# SCH_dito_2026-01-28.net
KiCad netlist of a schematic drawn in EasyEDA
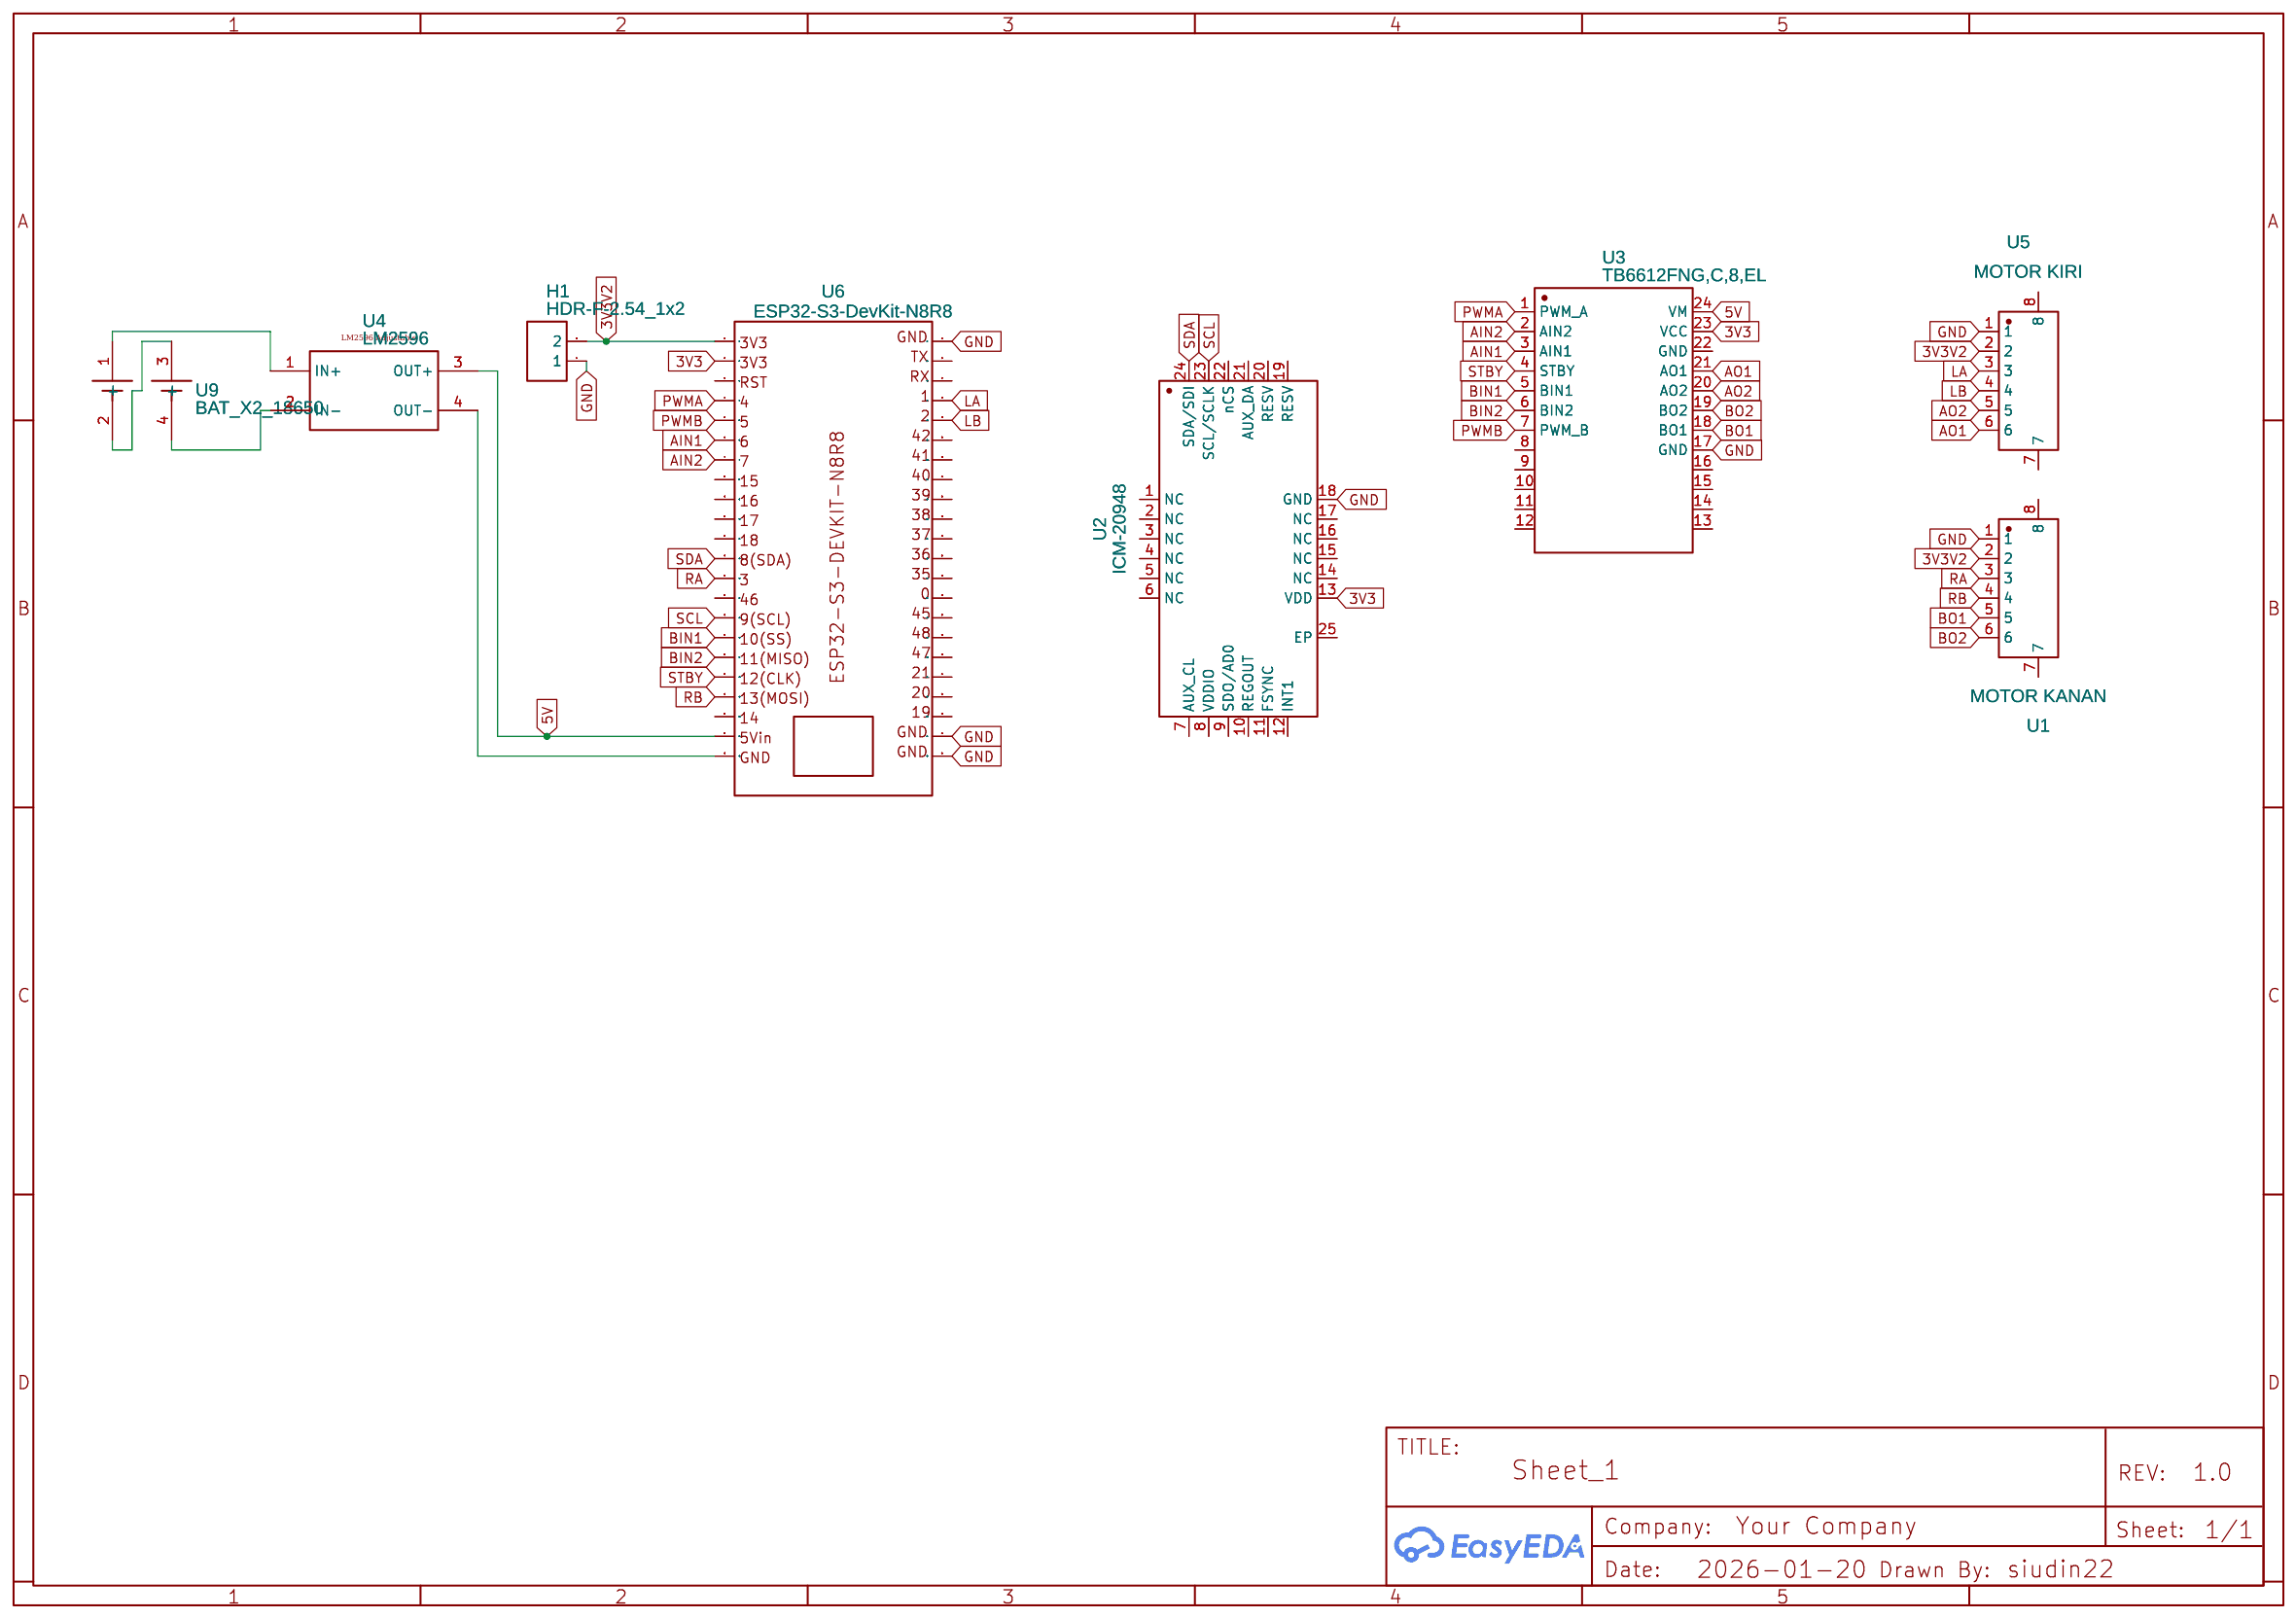
[diagram p0: Sheet_1]
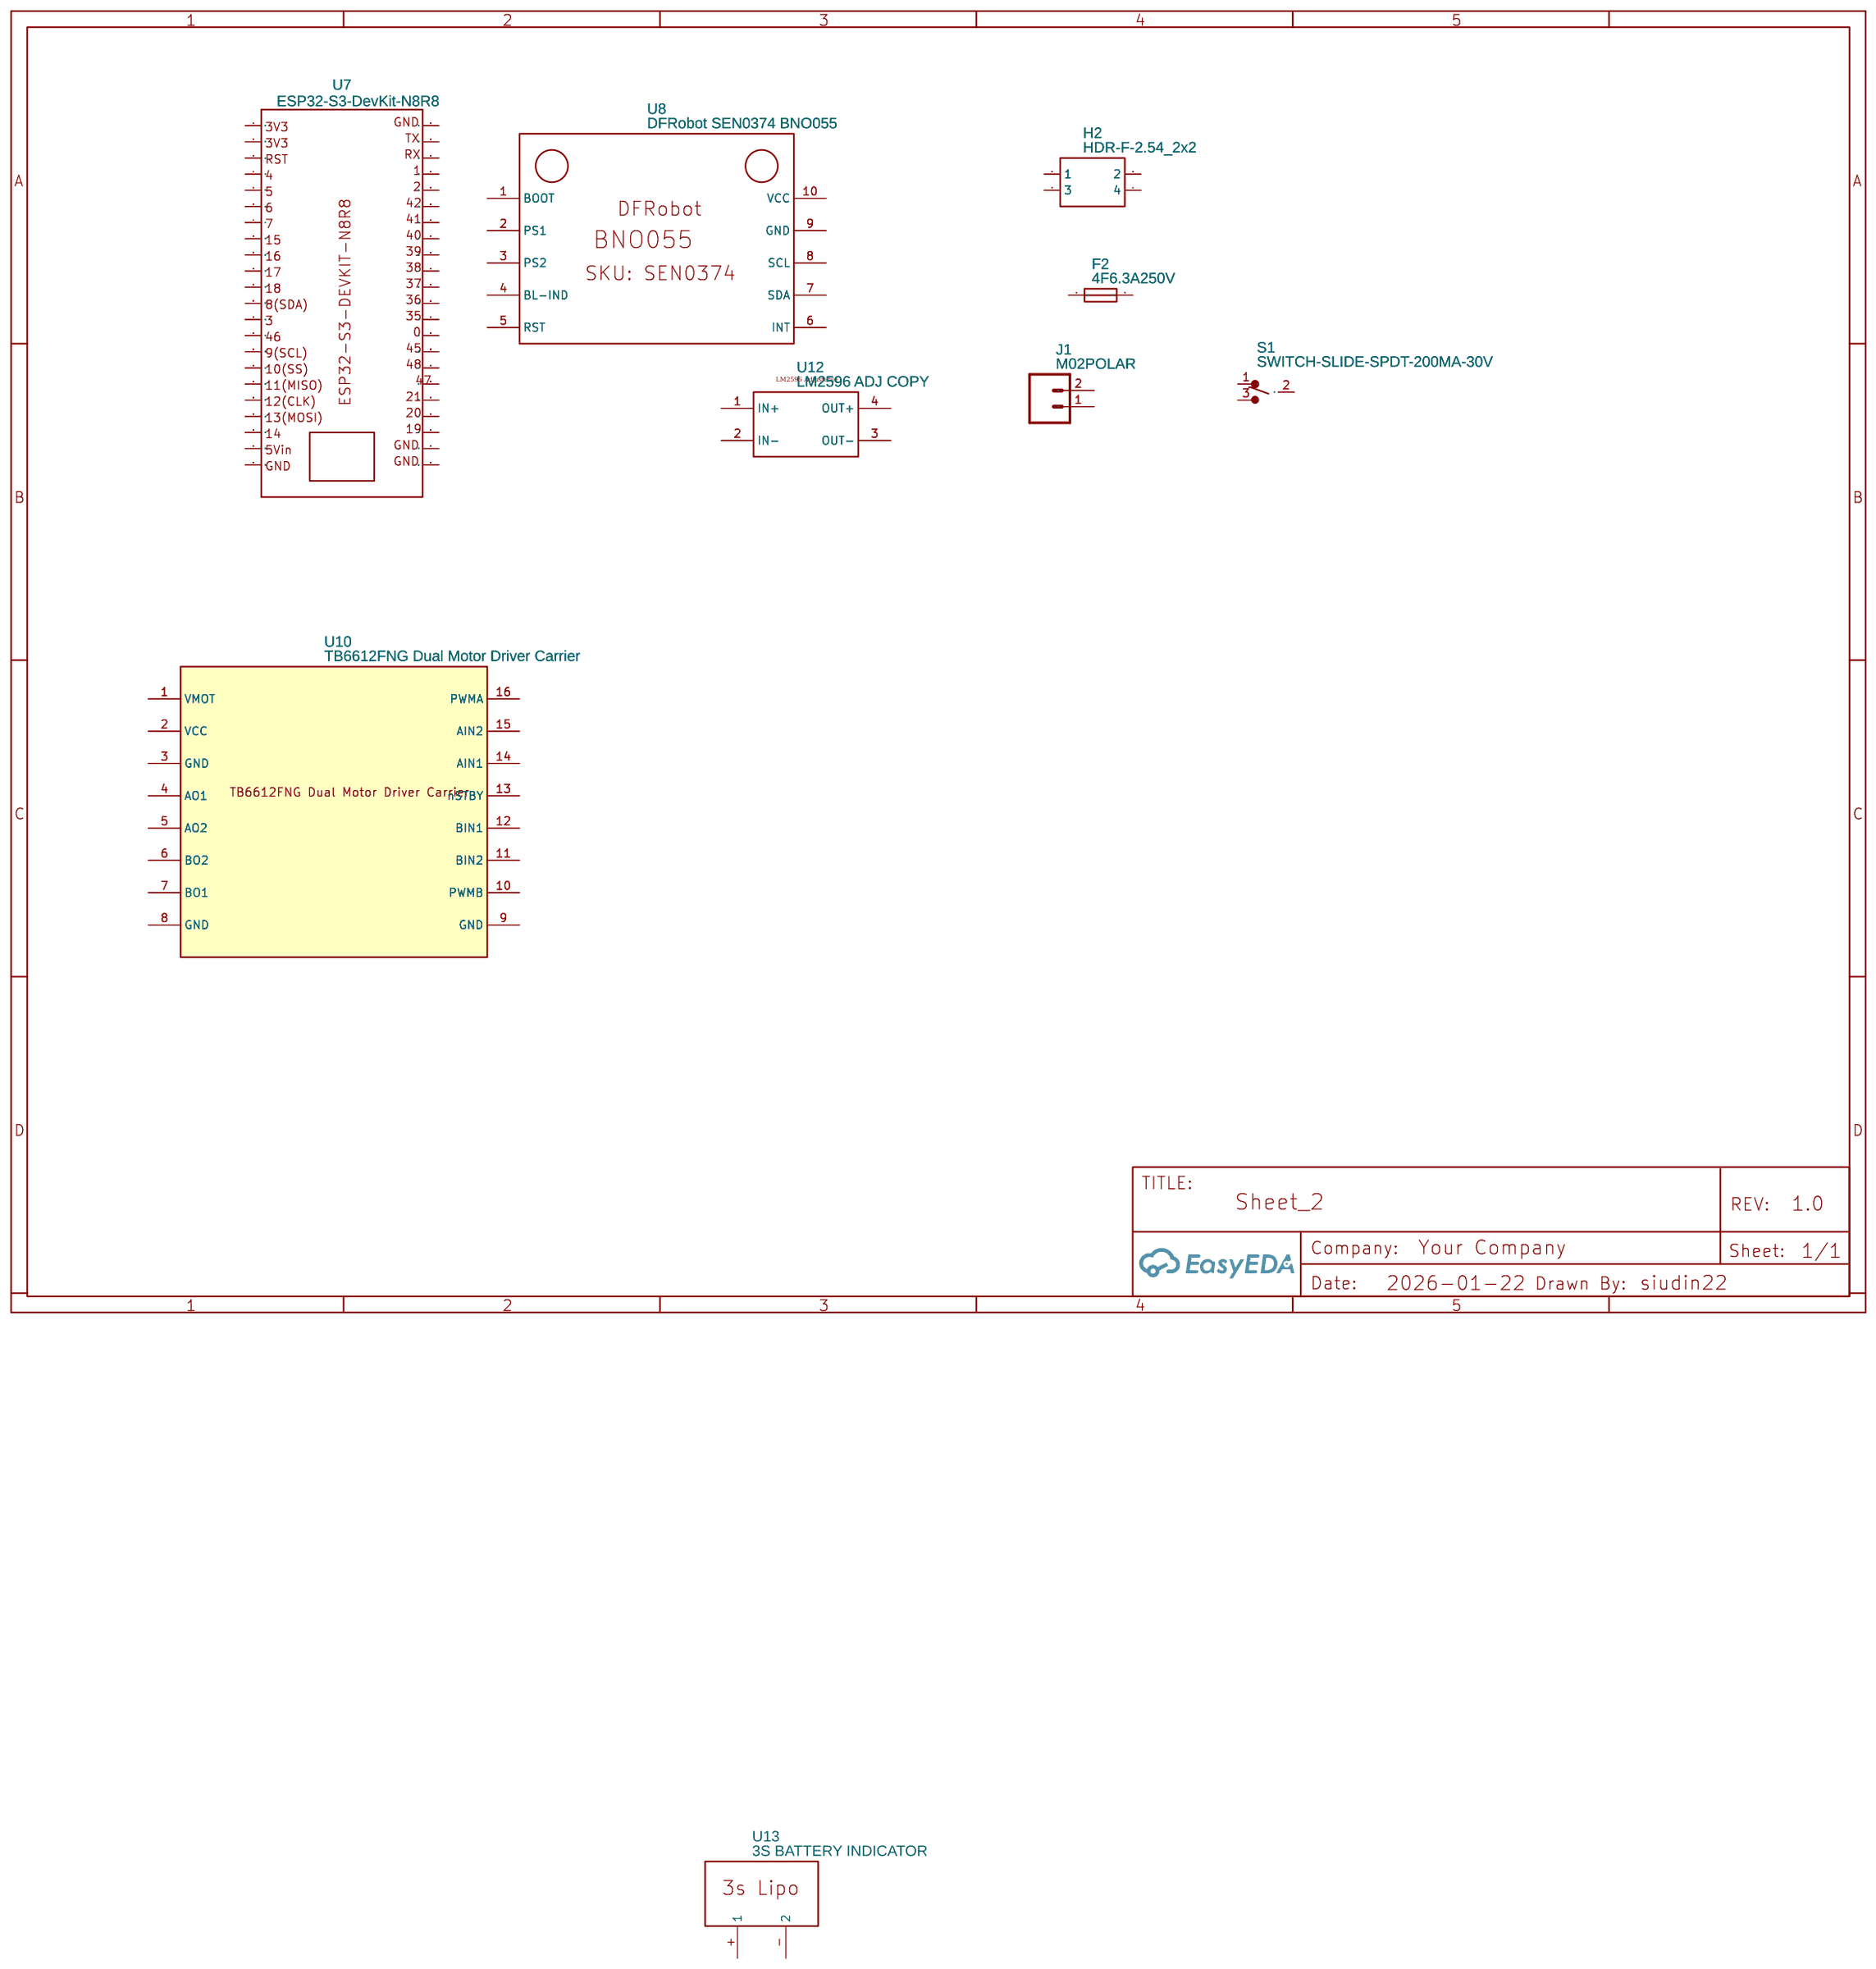
[diagram p1: Sheet_2]

(export (version "E")
  (design (tool "Eeschema 10.0.6"))
  (components
    (comp (ref "H1") (value "HDR-F-2.54_1x2") (libsource (lib "") (part "HDR-F-2.54_1x2")))
    (comp (ref "U1")
      (value "MOTOR KANAN")
      (fields (field (name "Manufacturer Part") "XY-SH1.0-6A61") (field (name "Manufacturer") "XYECONN(辛译)"))
      (libsource (lib "") (part "XY-SH1.0-6A61"))
    )
    (comp (ref "U2")
      (value "ICM-20948")
      (fields (field (name "Manufacturer") "TDK InvenSense(应美盛)"))
      (libsource (lib "") (part "ICM-20948"))
    )
    (comp (ref "U3")
      (value "TB6612FNG,C,8,EL")
      (fields (field (name "Manufacturer") "TOSHIBA(东芝)"))
      (libsource (lib "") (part "TB6612FNG,C,8,EL"))
    )
    (comp (ref "U4") (value "LM2596") (libsource (lib "") (part "BuckConverters_LM2596_Adj")))
    (comp (ref "U5")
      (value "MOTOR KIRI")
      (fields (field (name "Manufacturer Part") "XY-SH1.0-6A61") (field (name "Manufacturer") "XYECONN(辛译)"))
      (libsource (lib "") (part "XY-SH1.0-6A61"))
    )
    (comp (ref "U6")
      (value "ESP32-S3-DevKit-N8R8")
      (fields (field (name "Manufacturer") "WaveShare"))
      (libsource (lib "") (part "ESP32-S3-DevKit-N8R8"))
    )
    (comp (ref "U9")
      (value "BAT_X2_18650")
      (fields (field (name "Manufacturer") "Dex"))
      (libsource (lib "") (part "BAT_X2_18650"))
    )
    (comp (ref "F2")
      (value "4F6.3A250V")
      (fields (field (name "Manufacturer") "xcfuse(旭程)"))
      (libsource (lib "") (part "4F6.3A250V"))
    )
    (comp (ref "H2") (value "HDR-F-2.54_2x2") (libsource (lib "") (part "HDR-F-2.54_2x2")))
    (comp (ref "J1") (value "M02POLAR") (libsource (lib "") (part "M02POLAR")))
    (comp (ref "S1")
      (value "SWITCH-SLIDE-SPDT-200MA-30V")
      (libsource (lib "") (part "SWITCH-SLIDE-SPDT-200MA-30V"))
    )
    (comp (ref "U7")
      (value "ESP32-S3-DevKit-N8R8")
      (fields (field (name "Manufacturer") "WaveShare"))
      (libsource (lib "") (part "ESP32-S3-DevKit-N8R8"))
    )
    (comp (ref "U8") (value "DFRobot SEN0374 BNO055") (libsource (lib "") (part "DFRobot SEN0374 BNO055")))
    (comp (ref "U10")
      (value "TB6612FNG Dual Motor Driver Carrier")
      (libsource (lib "") (part "TB6612FNG Dual Motor Driver Carrier"))
    )
    (comp (ref "U12") (value "LM2596 ADJ COPY") (libsource (lib "") (part "BuckConverters_LM2596_Adj")))
    (comp (ref "U13") (value "3S BATTERY INDICATOR") (libsource (lib "") (part "3S BATTERY INDICATOR")))
  )
  (nets
    (net (code "1") (name "3V3") (class "Default")
      (node (ref "U2") (pin "13") (pinfunction "VDD_13") (pintype "unspecified"))
      (node (ref "U3") (pin "23") (pinfunction "VCC_23") (pintype "unspecified"))
      (node (ref "U6") (pin "2") (pinfunction "2_2") (pintype "unspecified"))
    )
    (net (code "2") (name "3V3V2") (class "Default")
      (node (ref "H1") (pin "2") (pinfunction "2_2") (pintype "input"))
      (node (ref "U1") (pin "2") (pinfunction "2_2") (pintype "unspecified"))
      (node (ref "U5") (pin "2") (pinfunction "2_2") (pintype "unspecified"))
      (node (ref "U6") (pin "1") (pinfunction "1_1") (pintype "unspecified"))
    )
    (net (code "3") (name "5V") (class "Default")
      (node (ref "U3") (pin "24") (pinfunction "VM_24") (pintype "unspecified"))
      (node (ref "U4") (pin "3") (pinfunction "OUT+_3") (pintype "unspecified"))
      (node (ref "U6") (pin "21") (pinfunction "21_21") (pintype "unspecified"))
    )
    (net (code "4") (name "AIN1") (class "Default")
      (node (ref "U3") (pin "3") (pinfunction "AIN1_3") (pintype "unspecified"))
      (node (ref "U6") (pin "6") (pinfunction "6_6") (pintype "unspecified"))
    )
    (net (code "5") (name "AIN2") (class "Default")
      (node (ref "U3") (pin "2") (pinfunction "AIN2_2") (pintype "unspecified"))
      (node (ref "U6") (pin "7") (pinfunction "7_7") (pintype "unspecified"))
    )
    (net (code "6") (name "AO1") (class "Default")
      (node (ref "U3") (pin "21") (pinfunction "AO1_21") (pintype "unspecified"))
      (node (ref "U5") (pin "6") (pinfunction "6_6") (pintype "unspecified"))
    )
    (net (code "7") (name "AO2") (class "Default")
      (node (ref "U3") (pin "20") (pinfunction "AO2_20") (pintype "unspecified"))
      (node (ref "U5") (pin "5") (pinfunction "5_5") (pintype "unspecified"))
    )
    (net (code "8") (name "BIN1") (class "Default")
      (node (ref "U3") (pin "5") (pinfunction "BIN1_5") (pintype "unspecified"))
      (node (ref "U6") (pin "16") (pinfunction "16_16") (pintype "unspecified"))
    )
    (net (code "9") (name "BIN2") (class "Default")
      (node (ref "U3") (pin "6") (pinfunction "BIN2_6") (pintype "unspecified"))
      (node (ref "U6") (pin "17") (pinfunction "17_17") (pintype "unspecified"))
    )
    (net (code "10") (name "BO1") (class "Default")
      (node (ref "U1") (pin "5") (pinfunction "5_5") (pintype "unspecified"))
      (node (ref "U3") (pin "18") (pinfunction "BO1_18") (pintype "unspecified"))
    )
    (net (code "11") (name "BO2") (class "Default")
      (node (ref "U1") (pin "6") (pinfunction "6_6") (pintype "unspecified"))
      (node (ref "U3") (pin "19") (pinfunction "BO2_19") (pintype "unspecified"))
    )
    (net (code "12") (name "GND") (class "Default")
      (node (ref "H1") (pin "1") (pinfunction "1_1") (pintype "input"))
      (node (ref "U1") (pin "1") (pinfunction "1_1") (pintype "unspecified"))
      (node (ref "U2") (pin "18") (pinfunction "GND_18") (pintype "unspecified"))
      (node (ref "U3") (pin "17") (pinfunction "GND_17") (pintype "unspecified"))
      (node (ref "U5") (pin "1") (pinfunction "1_1") (pintype "unspecified"))
      (node (ref "U6") (pin "23") (pinfunction "23_23") (pintype "unspecified"))
      (node (ref "U6") (pin "24") (pinfunction "24_24") (pintype "unspecified"))
      (node (ref "U6") (pin "44") (pinfunction "44_44") (pintype "unspecified"))
    )
    (net (code "13") (name "LA") (class "Default")
      (node (ref "U5") (pin "3") (pinfunction "3_3") (pintype "unspecified"))
      (node (ref "U6") (pin "41") (pinfunction "41_41") (pintype "unspecified"))
    )
    (net (code "14") (name "LB") (class "Default")
      (node (ref "U5") (pin "4") (pinfunction "4_4") (pintype "unspecified"))
      (node (ref "U6") (pin "40") (pinfunction "40_40") (pintype "unspecified"))
    )
    (net (code "15") (name "Net-(U4-IN+)") (class "Default")
      (node (ref "U4") (pin "1") (pinfunction "IN+_1") (pintype "unspecified"))
      (node (ref "U9") (pin "1") (pinfunction "+_1") (pintype "unspecified"))
    )
    (net (code "16") (name "Net-(U4-IN-)") (class "Default")
      (node (ref "U4") (pin "2") (pinfunction "IN-_2") (pintype "unspecified"))
      (node (ref "U9") (pin "4") (pinfunction "-_4") (pintype "unspecified"))
    )
    (net (code "17") (name "Net-(U4-OUT-)") (class "Default")
      (node (ref "U4") (pin "4") (pinfunction "OUT-_4") (pintype "unspecified"))
      (node (ref "U6") (pin "22") (pinfunction "22_22") (pintype "unspecified"))
    )
    (net (code "18") (name "Net-(U9-+-Pad3)") (class "Default")
      (node (ref "U9") (pin "2") (pinfunction "-_2") (pintype "unspecified"))
      (node (ref "U9") (pin "3") (pinfunction "+_3") (pintype "unspecified"))
    )
    (net (code "19") (name "PWMA") (class "Default")
      (node (ref "U3") (pin "1") (pinfunction "PWM_A_1") (pintype "unspecified"))
      (node (ref "U6") (pin "4") (pinfunction "4_4") (pintype "unspecified"))
    )
    (net (code "20") (name "PWMB") (class "Default")
      (node (ref "U3") (pin "7") (pinfunction "PWM_B_7") (pintype "unspecified"))
      (node (ref "U6") (pin "5") (pinfunction "5_5") (pintype "unspecified"))
    )
    (net (code "21") (name "RA") (class "Default")
      (node (ref "U1") (pin "3") (pinfunction "3_3") (pintype "unspecified"))
      (node (ref "U6") (pin "13") (pinfunction "13_13") (pintype "unspecified"))
    )
    (net (code "22") (name "RB") (class "Default")
      (node (ref "U1") (pin "4") (pinfunction "4_4") (pintype "unspecified"))
      (node (ref "U6") (pin "19") (pinfunction "19_19") (pintype "unspecified"))
    )
    (net (code "23") (name "SCL") (class "Default")
      (node (ref "U2") (pin "23") (pinfunction "SCL/SCLK_23") (pintype "unspecified"))
      (node (ref "U6") (pin "15") (pinfunction "15_15") (pintype "unspecified"))
    )
    (net (code "24") (name "SDA") (class "Default")
      (node (ref "U2") (pin "24") (pinfunction "SDA/SDI_24") (pintype "unspecified"))
      (node (ref "U6") (pin "12") (pinfunction "12_12") (pintype "unspecified"))
    )
    (net (code "25") (name "STBY") (class "Default")
      (node (ref "U3") (pin "4") (pinfunction "STBY_4") (pintype "unspecified"))
      (node (ref "U6") (pin "18") (pinfunction "18_18") (pintype "unspecified"))
    )
    (net (code "26") (name "unconnected-(F2-Pad1)") (class "Default")
      (node (ref "F2") (pin "1") (pinfunction "1_1") (pintype "unspecified"))
    )
    (net (code "27") (name "unconnected-(F2-Pad2)") (class "Default")
      (node (ref "F2") (pin "2") (pinfunction "2_2") (pintype "unspecified"))
    )
    (net (code "28") (name "unconnected-(H2-Pad1)") (class "Default")
      (node (ref "H2") (pin "1") (pinfunction "1_1") (pintype "unspecified"))
    )
    (net (code "29") (name "unconnected-(H2-Pad2)") (class "Default")
      (node (ref "H2") (pin "2") (pinfunction "2_2") (pintype "unspecified"))
    )
    (net (code "30") (name "unconnected-(H2-Pad3)") (class "Default")
      (node (ref "H2") (pin "3") (pinfunction "3_3") (pintype "unspecified"))
    )
    (net (code "31") (name "unconnected-(H2-Pad4)") (class "Default")
      (node (ref "H2") (pin "4") (pinfunction "4_4") (pintype "unspecified"))
    )
    (net (code "32") (name "unconnected-(J1-Pad1)") (class "Default")
      (node (ref "J1") (pin "1") (pinfunction "1_1") (pintype "bidirectional"))
    )
    (net (code "33") (name "unconnected-(J1-Pad2)") (class "Default")
      (node (ref "J1") (pin "2") (pinfunction "2_2") (pintype "bidirectional"))
    )
    (net (code "34") (name "unconnected-(S1-Pad1)") (class "Default")
      (node (ref "S1") (pin "1") (pinfunction "1_1") (pintype "input"))
    )
    (net (code "35") (name "unconnected-(S1-Pad2)") (class "Default")
      (node (ref "S1") (pin "2") (pinfunction "2_2") (pintype "input"))
    )
    (net (code "36") (name "unconnected-(S1-Pad3)") (class "Default")
      (node (ref "S1") (pin "3") (pinfunction "3_3") (pintype "input"))
    )
    (net (code "37") (name "unconnected-(U1-Pad7)") (class "Default")
      (node (ref "U1") (pin "7") (pinfunction "7_7") (pintype "unspecified"))
    )
    (net (code "38") (name "unconnected-(U1-Pad8)") (class "Default")
      (node (ref "U1") (pin "8") (pinfunction "8_8") (pintype "unspecified"))
    )
    (net (code "39") (name "unconnected-(U2-AUX_CL-Pad7)") (class "Default")
      (node (ref "U2") (pin "7") (pinfunction "AUX_CL_7") (pintype "unspecified"))
    )
    (net (code "40") (name "unconnected-(U2-AUX_DA-Pad21)") (class "Default")
      (node (ref "U2") (pin "21") (pinfunction "AUX_DA_21") (pintype "unspecified"))
    )
    (net (code "41") (name "unconnected-(U2-EP-Pad25)") (class "Default")
      (node (ref "U2") (pin "25") (pinfunction "EP_25") (pintype "unspecified"))
    )
    (net (code "42") (name "unconnected-(U2-FSYNC-Pad11)") (class "Default")
      (node (ref "U2") (pin "11") (pinfunction "FSYNC_11") (pintype "unspecified"))
    )
    (net (code "43") (name "unconnected-(U2-INT1-Pad12)") (class "Default")
      (node (ref "U2") (pin "12") (pinfunction "INT1_12") (pintype "unspecified"))
    )
    (net (code "44") (name "unconnected-(U2-NC-Pad1)") (class "Default")
      (node (ref "U2") (pin "1") (pinfunction "NC_1") (pintype "unspecified"))
    )
    (net (code "45") (name "unconnected-(U2-NC-Pad2)") (class "Default")
      (node (ref "U2") (pin "2") (pinfunction "NC_2") (pintype "unspecified"))
    )
    (net (code "46") (name "unconnected-(U2-NC-Pad3)") (class "Default")
      (node (ref "U2") (pin "3") (pinfunction "NC_3") (pintype "unspecified"))
    )
    (net (code "47") (name "unconnected-(U2-NC-Pad4)") (class "Default")
      (node (ref "U2") (pin "4") (pinfunction "NC_4") (pintype "unspecified"))
    )
    (net (code "48") (name "unconnected-(U2-NC-Pad5)") (class "Default")
      (node (ref "U2") (pin "5") (pinfunction "NC_5") (pintype "unspecified"))
    )
    (net (code "49") (name "unconnected-(U2-NC-Pad6)") (class "Default")
      (node (ref "U2") (pin "6") (pinfunction "NC_6") (pintype "unspecified"))
    )
    (net (code "50") (name "unconnected-(U2-NC-Pad14)") (class "Default")
      (node (ref "U2") (pin "14") (pinfunction "NC_14") (pintype "unspecified"))
    )
    (net (code "51") (name "unconnected-(U2-NC-Pad15)") (class "Default")
      (node (ref "U2") (pin "15") (pinfunction "NC_15") (pintype "unspecified"))
    )
    (net (code "52") (name "unconnected-(U2-NC-Pad16)") (class "Default")
      (node (ref "U2") (pin "16") (pinfunction "NC_16") (pintype "unspecified"))
    )
    (net (code "53") (name "unconnected-(U2-NC-Pad17)") (class "Default")
      (node (ref "U2") (pin "17") (pinfunction "NC_17") (pintype "unspecified"))
    )
    (net (code "54") (name "unconnected-(U2-REGOUT-Pad10)") (class "Default")
      (node (ref "U2") (pin "10") (pinfunction "REGOUT_10") (pintype "unspecified"))
    )
    (net (code "55") (name "unconnected-(U2-RESV-Pad19)") (class "Default")
      (node (ref "U2") (pin "19") (pinfunction "RESV_19") (pintype "unspecified"))
    )
    (net (code "56") (name "unconnected-(U2-RESV-Pad20)") (class "Default")
      (node (ref "U2") (pin "20") (pinfunction "RESV_20") (pintype "unspecified"))
    )
    (net (code "57") (name "unconnected-(U2-SDO{slash}AD0-Pad9)") (class "Default")
      (node (ref "U2") (pin "9") (pinfunction "SDO/AD0_9") (pintype "unspecified"))
    )
    (net (code "58") (name "unconnected-(U2-VDDIO-Pad8)") (class "Default")
      (node (ref "U2") (pin "8") (pinfunction "VDDIO_8") (pintype "unspecified"))
    )
    (net (code "59") (name "unconnected-(U2-nCS-Pad22)") (class "Default")
      (node (ref "U2") (pin "22") (pinfunction "nCS_22") (pintype "unspecified"))
    )
    (net (code "60") (name "unconnected-(U3-GND-Pad22)") (class "Default")
      (node (ref "U3") (pin "22") (pinfunction "GND_22") (pintype "unspecified"))
    )
    (net (code "61") (name "unconnected-(U3-Pad8)") (class "Default")
      (node (ref "U3") (pin "8") (pintype "unspecified"))
    )
    (net (code "62") (name "unconnected-(U3-Pad9)") (class "Default")
      (node (ref "U3") (pin "9") (pintype "unspecified"))
    )
    (net (code "63") (name "unconnected-(U3-Pad10)") (class "Default")
      (node (ref "U3") (pin "10") (pintype "unspecified"))
    )
    (net (code "64") (name "unconnected-(U3-Pad11)") (class "Default")
      (node (ref "U3") (pin "11") (pintype "unspecified"))
    )
    (net (code "65") (name "unconnected-(U3-Pad12)") (class "Default")
      (node (ref "U3") (pin "12") (pintype "unspecified"))
    )
    (net (code "66") (name "unconnected-(U3-Pad13)") (class "Default")
      (node (ref "U3") (pin "13") (pintype "unspecified"))
    )
    (net (code "67") (name "unconnected-(U3-Pad14)") (class "Default")
      (node (ref "U3") (pin "14") (pintype "unspecified"))
    )
    (net (code "68") (name "unconnected-(U3-Pad15)") (class "Default")
      (node (ref "U3") (pin "15") (pintype "unspecified"))
    )
    (net (code "69") (name "unconnected-(U3-Pad16)") (class "Default")
      (node (ref "U3") (pin "16") (pintype "unspecified"))
    )
    (net (code "70") (name "unconnected-(U5-Pad7)") (class "Default")
      (node (ref "U5") (pin "7") (pinfunction "7_7") (pintype "unspecified"))
    )
    (net (code "71") (name "unconnected-(U5-Pad8)") (class "Default")
      (node (ref "U5") (pin "8") (pinfunction "8_8") (pintype "unspecified"))
    )
    (net (code "72") (name "unconnected-(U6-Pad3)") (class "Default")
      (node (ref "U6") (pin "3") (pinfunction "3_3") (pintype "unspecified"))
    )
    (net (code "73") (name "unconnected-(U6-Pad8)") (class "Default")
      (node (ref "U6") (pin "8") (pinfunction "8_8") (pintype "unspecified"))
    )
    (net (code "74") (name "unconnected-(U6-Pad9)") (class "Default")
      (node (ref "U6") (pin "9") (pinfunction "9_9") (pintype "unspecified"))
    )
    (net (code "75") (name "unconnected-(U6-Pad10)") (class "Default")
      (node (ref "U6") (pin "10") (pinfunction "10_10") (pintype "unspecified"))
    )
    (net (code "76") (name "unconnected-(U6-Pad11)") (class "Default")
      (node (ref "U6") (pin "11") (pinfunction "11_11") (pintype "unspecified"))
    )
    (net (code "77") (name "unconnected-(U6-Pad14)") (class "Default")
      (node (ref "U6") (pin "14") (pinfunction "14_14") (pintype "unspecified"))
    )
    (net (code "78") (name "unconnected-(U6-Pad20)") (class "Default")
      (node (ref "U6") (pin "20") (pinfunction "20_20") (pintype "unspecified"))
    )
    (net (code "79") (name "unconnected-(U6-Pad25)") (class "Default")
      (node (ref "U6") (pin "25") (pinfunction "25_25") (pintype "unspecified"))
    )
    (net (code "80") (name "unconnected-(U6-Pad26)") (class "Default")
      (node (ref "U6") (pin "26") (pinfunction "26_26") (pintype "unspecified"))
    )
    (net (code "81") (name "unconnected-(U6-Pad27)") (class "Default")
      (node (ref "U6") (pin "27") (pinfunction "27_27") (pintype "unspecified"))
    )
    (net (code "82") (name "unconnected-(U6-Pad28)") (class "Default")
      (node (ref "U6") (pin "28") (pinfunction "28_28") (pintype "unspecified"))
    )
    (net (code "83") (name "unconnected-(U6-Pad29)") (class "Default")
      (node (ref "U6") (pin "29") (pinfunction "29_29") (pintype "unspecified"))
    )
    (net (code "84") (name "unconnected-(U6-Pad30)") (class "Default")
      (node (ref "U6") (pin "30") (pinfunction "30_30") (pintype "unspecified"))
    )
    (net (code "85") (name "unconnected-(U6-Pad31)") (class "Default")
      (node (ref "U6") (pin "31") (pinfunction "31_31") (pintype "unspecified"))
    )
    (net (code "86") (name "unconnected-(U6-Pad32)") (class "Default")
      (node (ref "U6") (pin "32") (pinfunction "32_32") (pintype "unspecified"))
    )
    (net (code "87") (name "unconnected-(U6-Pad33)") (class "Default")
      (node (ref "U6") (pin "33") (pinfunction "33_33") (pintype "unspecified"))
    )
    (net (code "88") (name "unconnected-(U6-Pad34)") (class "Default")
      (node (ref "U6") (pin "34") (pinfunction "34_34") (pintype "unspecified"))
    )
    (net (code "89") (name "unconnected-(U6-Pad35)") (class "Default")
      (node (ref "U6") (pin "35") (pinfunction "35_35") (pintype "unspecified"))
    )
    (net (code "90") (name "unconnected-(U6-Pad36)") (class "Default")
      (node (ref "U6") (pin "36") (pinfunction "36_36") (pintype "unspecified"))
    )
    (net (code "91") (name "unconnected-(U6-Pad37)") (class "Default")
      (node (ref "U6") (pin "37") (pinfunction "37_37") (pintype "unspecified"))
    )
    (net (code "92") (name "unconnected-(U6-Pad38)") (class "Default")
      (node (ref "U6") (pin "38") (pinfunction "38_38") (pintype "unspecified"))
    )
    (net (code "93") (name "unconnected-(U6-Pad39)") (class "Default")
      (node (ref "U6") (pin "39") (pinfunction "39_39") (pintype "unspecified"))
    )
    (net (code "94") (name "unconnected-(U6-Pad42)") (class "Default")
      (node (ref "U6") (pin "42") (pinfunction "42_42") (pintype "unspecified"))
    )
    (net (code "95") (name "unconnected-(U6-Pad43)") (class "Default")
      (node (ref "U6") (pin "43") (pinfunction "43_43") (pintype "unspecified"))
    )
    (net (code "96") (name "unconnected-(U7-Pad1)") (class "Default")
      (node (ref "U7") (pin "1") (pinfunction "1_1") (pintype "unspecified"))
    )
    (net (code "97") (name "unconnected-(U7-Pad2)") (class "Default")
      (node (ref "U7") (pin "2") (pinfunction "2_2") (pintype "unspecified"))
    )
    (net (code "98") (name "unconnected-(U7-Pad3)") (class "Default")
      (node (ref "U7") (pin "3") (pinfunction "3_3") (pintype "unspecified"))
    )
    (net (code "99") (name "unconnected-(U7-Pad4)") (class "Default")
      (node (ref "U7") (pin "4") (pinfunction "4_4") (pintype "unspecified"))
    )
    (net (code "100") (name "unconnected-(U7-Pad5)") (class "Default")
      (node (ref "U7") (pin "5") (pinfunction "5_5") (pintype "unspecified"))
    )
    (net (code "101") (name "unconnected-(U7-Pad6)") (class "Default")
      (node (ref "U7") (pin "6") (pinfunction "6_6") (pintype "unspecified"))
    )
    (net (code "102") (name "unconnected-(U7-Pad7)") (class "Default")
      (node (ref "U7") (pin "7") (pinfunction "7_7") (pintype "unspecified"))
    )
    (net (code "103") (name "unconnected-(U7-Pad8)") (class "Default")
      (node (ref "U7") (pin "8") (pinfunction "8_8") (pintype "unspecified"))
    )
    (net (code "104") (name "unconnected-(U7-Pad9)") (class "Default")
      (node (ref "U7") (pin "9") (pinfunction "9_9") (pintype "unspecified"))
    )
    (net (code "105") (name "unconnected-(U7-Pad10)") (class "Default")
      (node (ref "U7") (pin "10") (pinfunction "10_10") (pintype "unspecified"))
    )
    (net (code "106") (name "unconnected-(U7-Pad11)") (class "Default")
      (node (ref "U7") (pin "11") (pinfunction "11_11") (pintype "unspecified"))
    )
    (net (code "107") (name "unconnected-(U7-Pad12)") (class "Default")
      (node (ref "U7") (pin "12") (pinfunction "12_12") (pintype "unspecified"))
    )
    (net (code "108") (name "unconnected-(U7-Pad13)") (class "Default")
      (node (ref "U7") (pin "13") (pinfunction "13_13") (pintype "unspecified"))
    )
    (net (code "109") (name "unconnected-(U7-Pad14)") (class "Default")
      (node (ref "U7") (pin "14") (pinfunction "14_14") (pintype "unspecified"))
    )
    (net (code "110") (name "unconnected-(U7-Pad15)") (class "Default")
      (node (ref "U7") (pin "15") (pinfunction "15_15") (pintype "unspecified"))
    )
    (net (code "111") (name "unconnected-(U7-Pad16)") (class "Default")
      (node (ref "U7") (pin "16") (pinfunction "16_16") (pintype "unspecified"))
    )
    (net (code "112") (name "unconnected-(U7-Pad17)") (class "Default")
      (node (ref "U7") (pin "17") (pinfunction "17_17") (pintype "unspecified"))
    )
    (net (code "113") (name "unconnected-(U7-Pad18)") (class "Default")
      (node (ref "U7") (pin "18") (pinfunction "18_18") (pintype "unspecified"))
    )
    (net (code "114") (name "unconnected-(U7-Pad19)") (class "Default")
      (node (ref "U7") (pin "19") (pinfunction "19_19") (pintype "unspecified"))
    )
    (net (code "115") (name "unconnected-(U7-Pad20)") (class "Default")
      (node (ref "U7") (pin "20") (pinfunction "20_20") (pintype "unspecified"))
    )
    (net (code "116") (name "unconnected-(U7-Pad21)") (class "Default")
      (node (ref "U7") (pin "21") (pinfunction "21_21") (pintype "unspecified"))
    )
    (net (code "117") (name "unconnected-(U7-Pad22)") (class "Default")
      (node (ref "U7") (pin "22") (pinfunction "22_22") (pintype "unspecified"))
    )
    (net (code "118") (name "unconnected-(U7-Pad23)") (class "Default")
      (node (ref "U7") (pin "23") (pinfunction "23_23") (pintype "unspecified"))
    )
    (net (code "119") (name "unconnected-(U7-Pad24)") (class "Default")
      (node (ref "U7") (pin "24") (pinfunction "24_24") (pintype "unspecified"))
    )
    (net (code "120") (name "unconnected-(U7-Pad25)") (class "Default")
      (node (ref "U7") (pin "25") (pinfunction "25_25") (pintype "unspecified"))
    )
    (net (code "121") (name "unconnected-(U7-Pad26)") (class "Default")
      (node (ref "U7") (pin "26") (pinfunction "26_26") (pintype "unspecified"))
    )
    (net (code "122") (name "unconnected-(U7-Pad27)") (class "Default")
      (node (ref "U7") (pin "27") (pinfunction "27_27") (pintype "unspecified"))
    )
    (net (code "123") (name "unconnected-(U7-Pad28)") (class "Default")
      (node (ref "U7") (pin "28") (pinfunction "28_28") (pintype "unspecified"))
    )
    (net (code "124") (name "unconnected-(U7-Pad29)") (class "Default")
      (node (ref "U7") (pin "29") (pinfunction "29_29") (pintype "unspecified"))
    )
    (net (code "125") (name "unconnected-(U7-Pad30)") (class "Default")
      (node (ref "U7") (pin "30") (pinfunction "30_30") (pintype "unspecified"))
    )
    (net (code "126") (name "unconnected-(U7-Pad31)") (class "Default")
      (node (ref "U7") (pin "31") (pinfunction "31_31") (pintype "unspecified"))
    )
    (net (code "127") (name "unconnected-(U7-Pad32)") (class "Default")
      (node (ref "U7") (pin "32") (pinfunction "32_32") (pintype "unspecified"))
    )
    (net (code "128") (name "unconnected-(U7-Pad33)") (class "Default")
      (node (ref "U7") (pin "33") (pinfunction "33_33") (pintype "unspecified"))
    )
    (net (code "129") (name "unconnected-(U7-Pad34)") (class "Default")
      (node (ref "U7") (pin "34") (pinfunction "34_34") (pintype "unspecified"))
    )
    (net (code "130") (name "unconnected-(U7-Pad35)") (class "Default")
      (node (ref "U7") (pin "35") (pinfunction "35_35") (pintype "unspecified"))
    )
    (net (code "131") (name "unconnected-(U7-Pad36)") (class "Default")
      (node (ref "U7") (pin "36") (pinfunction "36_36") (pintype "unspecified"))
    )
    (net (code "132") (name "unconnected-(U7-Pad37)") (class "Default")
      (node (ref "U7") (pin "37") (pinfunction "37_37") (pintype "unspecified"))
    )
    (net (code "133") (name "unconnected-(U7-Pad38)") (class "Default")
      (node (ref "U7") (pin "38") (pinfunction "38_38") (pintype "unspecified"))
    )
    (net (code "134") (name "unconnected-(U7-Pad39)") (class "Default")
      (node (ref "U7") (pin "39") (pinfunction "39_39") (pintype "unspecified"))
    )
    (net (code "135") (name "unconnected-(U7-Pad40)") (class "Default")
      (node (ref "U7") (pin "40") (pinfunction "40_40") (pintype "unspecified"))
    )
    (net (code "136") (name "unconnected-(U7-Pad41)") (class "Default")
      (node (ref "U7") (pin "41") (pinfunction "41_41") (pintype "unspecified"))
    )
    (net (code "137") (name "unconnected-(U7-Pad42)") (class "Default")
      (node (ref "U7") (pin "42") (pinfunction "42_42") (pintype "unspecified"))
    )
    (net (code "138") (name "unconnected-(U7-Pad43)") (class "Default")
      (node (ref "U7") (pin "43") (pinfunction "43_43") (pintype "unspecified"))
    )
    (net (code "139") (name "unconnected-(U7-Pad44)") (class "Default")
      (node (ref "U7") (pin "44") (pinfunction "44_44") (pintype "unspecified"))
    )
    (net (code "140") (name "unconnected-(U8-BL-IND-Pad4)") (class "Default")
      (node (ref "U8") (pin "4") (pinfunction "BL-IND_4") (pintype "unspecified"))
    )
    (net (code "141") (name "unconnected-(U8-BOOT-Pad1)") (class "Default")
      (node (ref "U8") (pin "1") (pinfunction "BOOT_1") (pintype "unspecified"))
    )
    (net (code "142") (name "unconnected-(U8-GND-Pad9)") (class "Default")
      (node (ref "U8") (pin "9") (pinfunction "GND_9") (pintype "unspecified"))
    )
    (net (code "143") (name "unconnected-(U8-INT-Pad6)") (class "Default")
      (node (ref "U8") (pin "6") (pinfunction "INT_6") (pintype "unspecified"))
    )
    (net (code "144") (name "unconnected-(U8-PS1-Pad2)") (class "Default")
      (node (ref "U8") (pin "2") (pinfunction "PS1_2") (pintype "unspecified"))
    )
    (net (code "145") (name "unconnected-(U8-PS2-Pad3)") (class "Default")
      (node (ref "U8") (pin "3") (pinfunction "PS2_3") (pintype "unspecified"))
    )
    (net (code "146") (name "unconnected-(U8-RST-Pad5)") (class "Default")
      (node (ref "U8") (pin "5") (pinfunction "RST_5") (pintype "unspecified"))
    )
    (net (code "147") (name "unconnected-(U8-SCL-Pad8)") (class "Default")
      (node (ref "U8") (pin "8") (pinfunction "SCL_8") (pintype "unspecified"))
    )
    (net (code "148") (name "unconnected-(U8-SDA-Pad7)") (class "Default")
      (node (ref "U8") (pin "7") (pinfunction "SDA_7") (pintype "unspecified"))
    )
    (net (code "149") (name "unconnected-(U8-VCC-Pad10)") (class "Default")
      (node (ref "U8") (pin "10") (pinfunction "VCC_10") (pintype "unspecified"))
    )
    (net (code "150") (name "unconnected-(U10-AIN1-Pad14)") (class "Default")
      (node (ref "U10") (pin "14") (pinfunction "AIN1_14") (pintype "unspecified"))
    )
    (net (code "151") (name "unconnected-(U10-AIN2-Pad15)") (class "Default")
      (node (ref "U10") (pin "15") (pinfunction "AIN2_15") (pintype "unspecified"))
    )
    (net (code "152") (name "unconnected-(U10-AO1-Pad4)") (class "Default")
      (node (ref "U10") (pin "4") (pinfunction "AO1_4") (pintype "unspecified"))
    )
    (net (code "153") (name "unconnected-(U10-AO2-Pad5)") (class "Default")
      (node (ref "U10") (pin "5") (pinfunction "AO2_5") (pintype "unspecified"))
    )
    (net (code "154") (name "unconnected-(U10-BIN1-Pad12)") (class "Default")
      (node (ref "U10") (pin "12") (pinfunction "BIN1_12") (pintype "unspecified"))
    )
    (net (code "155") (name "unconnected-(U10-BIN2-Pad11)") (class "Default")
      (node (ref "U10") (pin "11") (pinfunction "BIN2_11") (pintype "unspecified"))
    )
    (net (code "156") (name "unconnected-(U10-BO1-Pad7)") (class "Default")
      (node (ref "U10") (pin "7") (pinfunction "BO1_7") (pintype "unspecified"))
    )
    (net (code "157") (name "unconnected-(U10-BO2-Pad6)") (class "Default")
      (node (ref "U10") (pin "6") (pinfunction "BO2_6") (pintype "unspecified"))
    )
    (net (code "158") (name "unconnected-(U10-GND-Pad3)") (class "Default")
      (node (ref "U10") (pin "3") (pinfunction "GND_3") (pintype "unspecified"))
    )
    (net (code "159") (name "unconnected-(U10-GND-Pad8)") (class "Default")
      (node (ref "U10") (pin "8") (pinfunction "GND_8") (pintype "unspecified"))
    )
    (net (code "160") (name "unconnected-(U10-GND-Pad9)") (class "Default")
      (node (ref "U10") (pin "9") (pinfunction "GND_9") (pintype "unspecified"))
    )
    (net (code "161") (name "unconnected-(U10-PWMA-Pad16)") (class "Default")
      (node (ref "U10") (pin "16") (pinfunction "PWMA_16") (pintype "unspecified"))
    )
    (net (code "162") (name "unconnected-(U10-PWMB-Pad10)") (class "Default")
      (node (ref "U10") (pin "10") (pinfunction "PWMB_10") (pintype "unspecified"))
    )
    (net (code "163") (name "unconnected-(U10-VCC-Pad2)") (class "Default")
      (node (ref "U10") (pin "2") (pinfunction "VCC_2") (pintype "unspecified"))
    )
    (net (code "164") (name "unconnected-(U10-VMOT-Pad1)") (class "Default")
      (node (ref "U10") (pin "1") (pinfunction "VMOT_1") (pintype "unspecified"))
    )
    (net (code "165") (name "unconnected-(U10-nSTBY-Pad13)") (class "Default")
      (node (ref "U10") (pin "13") (pinfunction "nSTBY_13") (pintype "unspecified"))
    )
    (net (code "166") (name "unconnected-(U12-IN+-Pad1)") (class "Default")
      (node (ref "U12") (pin "1") (pinfunction "IN+_1") (pintype "unspecified"))
    )
    (net (code "167") (name "unconnected-(U12-IN--Pad2)") (class "Default")
      (node (ref "U12") (pin "2") (pinfunction "IN-_2") (pintype "unspecified"))
    )
    (net (code "168") (name "unconnected-(U12-OUT+-Pad4)") (class "Default")
      (node (ref "U12") (pin "4") (pinfunction "OUT+_4") (pintype "unspecified"))
    )
    (net (code "169") (name "unconnected-(U12-OUT--Pad3)") (class "Default")
      (node (ref "U12") (pin "3") (pinfunction "OUT-_3") (pintype "unspecified"))
    )
    (net (code "170") (name "unconnected-(U13-1-Pad+)") (class "Default")
      (node (ref "U13") (pin "+") (pinfunction "1_+") (pintype "unspecified"))
    )
    (net (code "171") (name "unconnected-(U13-2-Pad-)") (class "Default")
      (node (ref "U13") (pin "-") (pinfunction "2_-") (pintype "unspecified"))
    )
  )
)
